# Sheet2.net
KiCad netlist of a schematic drawn in Altium Designer
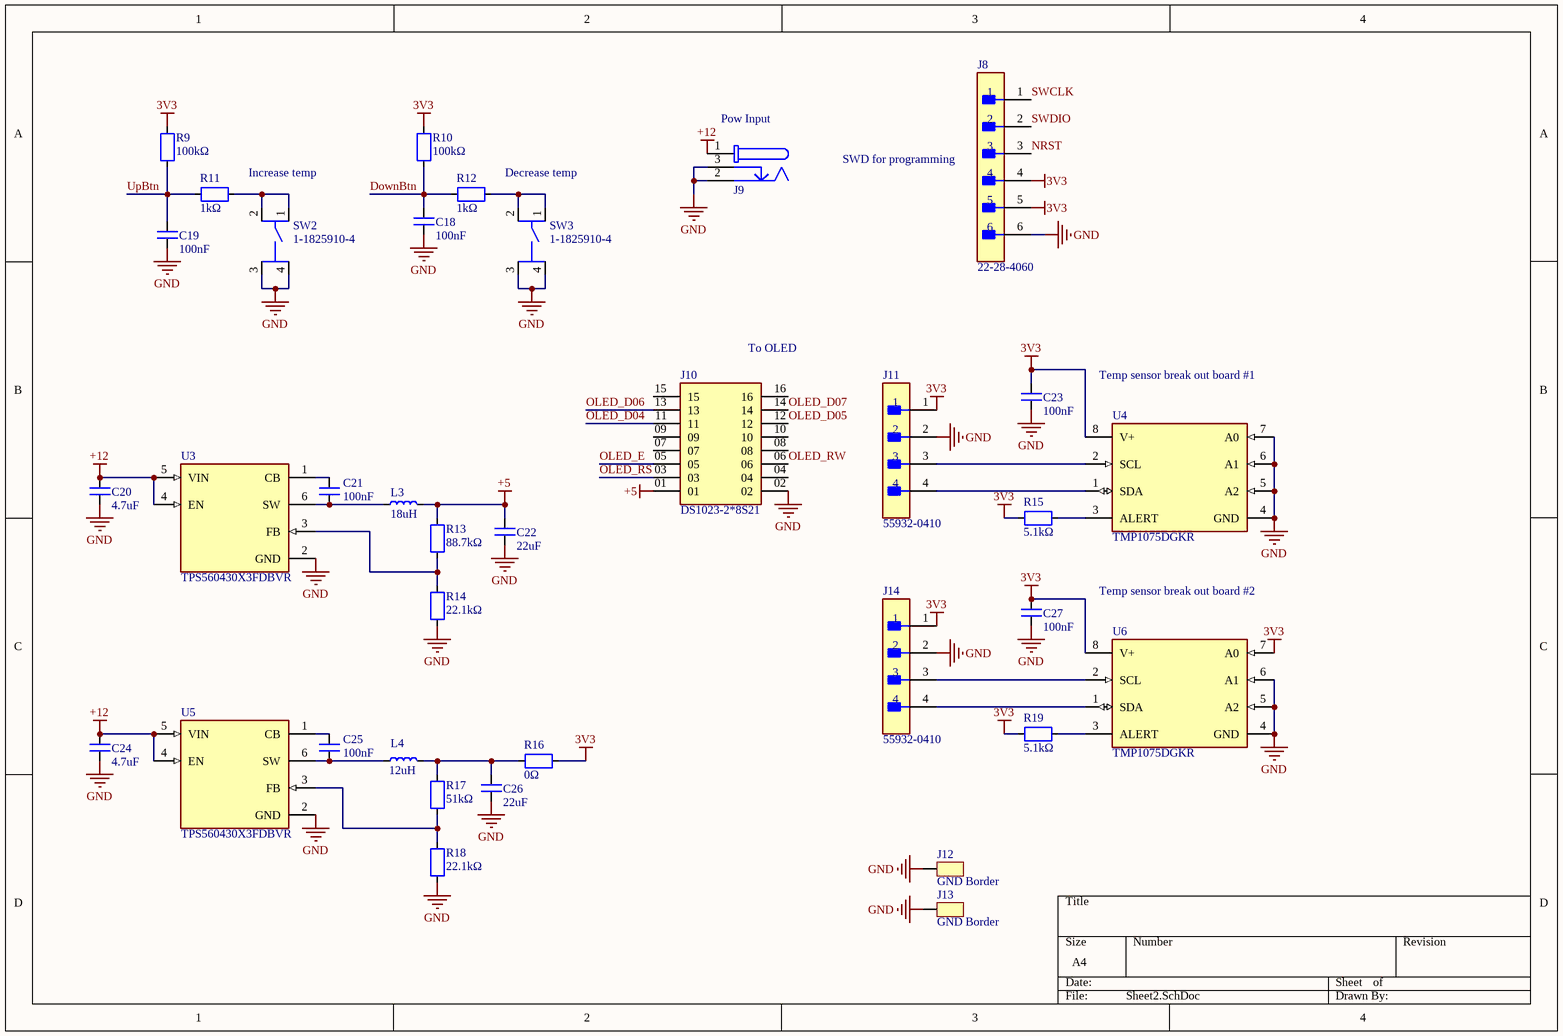
[diagram p0: Sheet2.SchDoc]

(export (version "E")
  (design (tool "Eeschema 10.0.6"))
  (components
    (comp (ref "C18") (value "100nF") (footprint "0603 Imperial") (libsource (lib "Schlib1") (part "0603 C")))
    (comp (ref "C19") (value "100nF") (footprint "0603 Imperial") (libsource (lib "Schlib1") (part "0603 C")))
    (comp (ref "C20") (value "4.7uF") (footprint "0603 Imperial") (libsource (lib "Schlib1") (part "0603 C")))
    (comp (ref "C21") (value "100nF") (footprint "0603 Imperial") (libsource (lib "Schlib1") (part "0603 C")))
    (comp (ref "C22") (value "22uF") (footprint "0603 Imperial") (libsource (lib "Schlib1") (part "0603 C")))
    (comp (ref "C23") (value "100nF") (footprint "0603 Imperial") (libsource (lib "Schlib1") (part "0603 C")))
    (comp (ref "C24") (value "4.7uF") (footprint "0603 Imperial") (libsource (lib "Schlib1") (part "0603 C")))
    (comp (ref "C25") (value "100nF") (footprint "0603 Imperial") (libsource (lib "Schlib1") (part "0603 C")))
    (comp (ref "C26") (value "22uF") (footprint "0603 Imperial") (libsource (lib "Schlib1") (part "0603 C")))
    (comp (ref "C27") (value "100nF") (footprint "0603 Imperial") (libsource (lib "Schlib1") (part "0603 C")))
    (comp (ref "J8")
      (value "22-28-4060")
      (footprint "FP-22-28-4060-MFG")
      (description "CONN HEADER VERT 6POS 2.54MM")
      (libsource (lib "Schlib1") (part "6 pin header"))
    )
    (comp (ref "J9")
      (value "694106105102")
      (footprint "694108105102")
      (description "WR-DC DC Power Jack Connector, Male, Right Angled, 24V, 5A")
      (fields (field (name "MANUFACTURER") "Wurth Elektronik"))
      (libsource (lib "Schlib1") (part "694106105102"))
    )
    (comp (ref "J10")
      (value "DS1023-2*8S21")
      (footprint "16 pin header")
      (description "SSQ - Samtec 2.54mm Square Tail Dual Row Socket Strip 8.5mm Profile - Fast Stock")
      (fields (field (name "MF") "Samtec") (field (name "MP") "SSQ-108-XX-X-D"))
      (libsource (lib "Schlib1") (part "DS1023-2*8S21"))
    )
    (comp (ref "J11")
      (value "55932-0410")
      (footprint "Wire Solder Pads")
      (description "CONN HEADER VERT 4POS 2MM")
      (libsource (lib "Schlib1") (part "Wire Solder pads"))
    )
    (comp (ref "J12")
      (value "GND Border")
      (footprint "GND Border")
      (libsource (lib "Schlib1") (part "GND Border"))
    )
    (comp (ref "J13")
      (value "GND Border")
      (footprint "GND Border")
      (libsource (lib "Schlib1") (part "GND Border"))
    )
    (comp (ref "J14")
      (value "55932-0410")
      (footprint "Wire Solder Pads")
      (description "CONN HEADER VERT 4POS 2MM")
      (libsource (lib "Schlib1") (part "Wire Solder pads"))
    )
    (comp (ref "L3")
      (value "18uH")
      (footprint "IND_SRR6038-180Y")
      (description "Ind6.8x6.8x3.8mm,18uH30%1.5A,shdSMD ¦ Bourns SRR6038-180Y")
      (fields (field (name "MF") "Bourns") (field (name "MP") "SRR6038-180Y"))
      (libsource (lib "Schlib1") (part "18uH"))
    )
    (comp (ref "L4")
      (value "12uH")
      (footprint "WE-PD2SR_7850")
      (description "WE-PD2SR SMT Power Inductor, size 7850, 1.2µH, 4.85A, 13mΩ")
      (fields
        (field (name "MANUFACTURER PART NUMBER") "744787012")
        (field (name "MANUFACTURER") "Wurth Elektronik")
      )
      (libsource (lib "Schlib1") (part "12uH"))
    )
    (comp (ref "R9") (value "100kΩ") (footprint "0603 Imperial") (libsource (lib "Schlib1") (part "0603 R")))
    (comp (ref "R10") (value "100kΩ") (footprint "0603 Imperial") (libsource (lib "Schlib1") (part "0603 R")))
    (comp (ref "R11") (value "1kΩ") (footprint "0603 Imperial") (libsource (lib "Schlib1") (part "0603 R")))
    (comp (ref "R12") (value "1kΩ") (footprint "0603 Imperial") (libsource (lib "Schlib1") (part "0603 R")))
    (comp (ref "R13")
      (value "88.7kΩ")
      (footprint "0603 Imperial")
      (libsource (lib "Schlib1") (part "0603 R"))
    )
    (comp (ref "R14")
      (value "22.1kΩ")
      (footprint "0603 Imperial")
      (libsource (lib "Schlib1") (part "0603 R"))
    )
    (comp (ref "R15") (value "5.1kΩ") (footprint "0603 Imperial") (libsource (lib "Schlib1") (part "0603 R")))
    (comp (ref "R16") (value "0Ω") (footprint "0603 Imperial") (libsource (lib "Schlib1") (part "0603 R")))
    (comp (ref "R17") (value "51kΩ") (footprint "0603 Imperial") (libsource (lib "Schlib1") (part "0603 R")))
    (comp (ref "R18")
      (value "22.1kΩ")
      (footprint "0603 Imperial")
      (libsource (lib "Schlib1") (part "0603 R"))
    )
    (comp (ref "R19") (value "5.1kΩ") (footprint "0603 Imperial") (libsource (lib "Schlib1") (part "0603 R")))
    (comp (ref "SW2")
      (value "1-1825910-4")
      (footprint "TE_1-1825910-4")
      (description "Switch Tactile OFF _ON_ SPST Round Button PC Pins 0.05A 24VDC 100000Cycles 1.56N Thru-Hole")
      (fields (field (name "MF") "TE Connectivity"))
      (libsource (lib "Schlib1") (part "1-1825910-4"))
    )
    (comp (ref "SW3")
      (value "1-1825910-4")
      (footprint "TE_1-1825910-4")
      (description "Switch Tactile OFF _ON_ SPST Round Button PC Pins 0.05A 24VDC 100000Cycles 1.56N Thru-Hole")
      (fields (field (name "MF") "TE Connectivity"))
      (libsource (lib "Schlib1") (part "1-1825910-4"))
    )
    (comp (ref "U3")
      (value "TPS560430X3FDBVR")
      (footprint "Buck")
      (fields (field (name "MF") "{'manufacturer': u'Texas Instruments'}"))
      (libsource (lib "Schlib1") (part "Buck"))
    )
    (comp (ref "U4")
      (value "TMP1075DGKR")
      (footprint "FP-DGK0008A-IPC_A")
      (description "SENSOR TEMPERATURE")
      (libsource (lib "Schlib1") (part "CMP-04948-000063-1"))
    )
    (comp (ref "U5")
      (value "TPS560430X3FDBVR")
      (footprint "Buck")
      (fields (field (name "MF") "{'manufacturer': u'Texas Instruments'}"))
      (libsource (lib "Schlib1") (part "Buck"))
    )
    (comp (ref "U6")
      (value "TMP1075DGKR")
      (footprint "FP-DGK0008A-IPC_A")
      (description "SENSOR TEMPERATURE")
      (libsource (lib "Schlib1") (part "CMP-04948-000063-1"))
    )
  )
  (nets
    (net (code "1") (name "+5") (class "Default")
      (node (ref "C22") (pin "1") (pinfunction "1_1") (pintype "passive"))
      (node (ref "J10") (pin "01") (pinfunction "01_01") (pintype "passive"))
      (node (ref "L3") (pin "2") (pinfunction "2_2") (pintype "passive"))
      (node (ref "R13") (pin "2") (pinfunction "2_2") (pintype "passive"))
    )
    (net (code "2") (name "+12") (class "Default")
      (node (ref "C20") (pin "1") (pinfunction "1_1") (pintype "passive"))
      (node (ref "C24") (pin "1") (pinfunction "1_1") (pintype "passive"))
      (node (ref "J9") (pin "1") (pinfunction "1_1") (pintype "passive"))
      (node (ref "U3") (pin "4") (pinfunction "EN_4") (pintype "input"))
      (node (ref "U3") (pin "5") (pinfunction "VIN_5") (pintype "input"))
      (node (ref "U5") (pin "4") (pinfunction "EN_4") (pintype "input"))
      (node (ref "U5") (pin "5") (pinfunction "VIN_5") (pintype "input"))
    )
    (net (code "3") (name "/DownBtn") (class "Default")
      (node (ref "C18") (pin "1") (pinfunction "1_1") (pintype "passive"))
      (node (ref "R10") (pin "1") (pinfunction "1_1") (pintype "passive"))
      (node (ref "R12") (pin "2") (pinfunction "2_2") (pintype "passive"))
    )
    (net (code "4") (name "/NRST") (class "Default")
      (node (ref "J8") (pin "3") (pinfunction "3_3") (pintype "passive"))
    )
    (net (code "5") (name "/OLED_D04") (class "Default")
      (node (ref "J10") (pin "11") (pinfunction "11_11") (pintype "passive"))
    )
    (net (code "6") (name "/OLED_D05") (class "Default")
      (node (ref "J10") (pin "12") (pinfunction "12_12") (pintype "passive"))
    )
    (net (code "7") (name "/OLED_D06") (class "Default")
      (node (ref "J10") (pin "13") (pinfunction "13_13") (pintype "passive"))
    )
    (net (code "8") (name "/OLED_D07") (class "Default")
      (node (ref "J10") (pin "14") (pinfunction "14_14") (pintype "passive"))
    )
    (net (code "9") (name "/OLED_E") (class "Default")
      (node (ref "J10") (pin "05") (pinfunction "05_05") (pintype "passive"))
    )
    (net (code "10") (name "/OLED_RS") (class "Default")
      (node (ref "J10") (pin "03") (pinfunction "03_03") (pintype "passive"))
    )
    (net (code "11") (name "/OLED_RW") (class "Default")
      (node (ref "J10") (pin "06") (pinfunction "06_06") (pintype "passive"))
    )
    (net (code "12") (name "/SWCLK") (class "Default")
      (node (ref "J8") (pin "1") (pinfunction "1_1") (pintype "passive"))
    )
    (net (code "13") (name "/SWDIO") (class "Default")
      (node (ref "J8") (pin "2") (pinfunction "2_2") (pintype "passive"))
    )
    (net (code "14") (name "/UpBtn") (class "Default")
      (node (ref "C19") (pin "1") (pinfunction "1_1") (pintype "passive"))
      (node (ref "R11") (pin "2") (pinfunction "2_2") (pintype "passive"))
      (node (ref "R9") (pin "1") (pinfunction "1_1") (pintype "passive"))
    )
    (net (code "15") (name "3V3") (class "Default")
      (node (ref "C23") (pin "2") (pinfunction "2_2") (pintype "passive"))
      (node (ref "C27") (pin "2") (pinfunction "2_2") (pintype "passive"))
      (node (ref "J11") (pin "1") (pinfunction "1_1") (pintype "passive"))
      (node (ref "J14") (pin "1") (pinfunction "1_1") (pintype "passive"))
      (node (ref "J8") (pin "4") (pinfunction "4_4") (pintype "passive"))
      (node (ref "J8") (pin "5") (pinfunction "5_5") (pintype "passive"))
      (node (ref "R10") (pin "2") (pinfunction "2_2") (pintype "passive"))
      (node (ref "R15") (pin "2") (pinfunction "2_2") (pintype "passive"))
      (node (ref "R16") (pin "2") (pinfunction "2_2") (pintype "passive"))
      (node (ref "R19") (pin "2") (pinfunction "2_2") (pintype "passive"))
      (node (ref "R9") (pin "2") (pinfunction "2_2") (pintype "passive"))
      (node (ref "U4") (pin "8") (pinfunction "V+_8") (pintype "power_in"))
      (node (ref "U6") (pin "7") (pinfunction "A0_7") (pintype "input"))
      (node (ref "U6") (pin "8") (pinfunction "V+_8") (pintype "power_in"))
    )
    (net (code "16") (name "GND") (class "Default")
      (node (ref "C18") (pin "2") (pinfunction "2_2") (pintype "passive"))
      (node (ref "C19") (pin "2") (pinfunction "2_2") (pintype "passive"))
      (node (ref "C20") (pin "2") (pinfunction "2_2") (pintype "passive"))
      (node (ref "C22") (pin "2") (pinfunction "2_2") (pintype "passive"))
      (node (ref "C23") (pin "1") (pinfunction "1_1") (pintype "passive"))
      (node (ref "C24") (pin "2") (pinfunction "2_2") (pintype "passive"))
      (node (ref "C26") (pin "2") (pinfunction "2_2") (pintype "passive"))
      (node (ref "C27") (pin "1") (pinfunction "1_1") (pintype "passive"))
      (node (ref "J10") (pin "02") (pinfunction "02_02") (pintype "passive"))
      (node (ref "J11") (pin "2") (pinfunction "2_2") (pintype "passive"))
      (node (ref "J12") (pin "0") (pinfunction "0_0") (pintype "passive"))
      (node (ref "J13") (pin "0") (pinfunction "0_0") (pintype "passive"))
      (node (ref "J14") (pin "2") (pinfunction "2_2") (pintype "passive"))
      (node (ref "J8") (pin "6") (pinfunction "6_6") (pintype "passive"))
      (node (ref "J9") (pin "2") (pinfunction "2_2") (pintype "passive"))
      (node (ref "J9") (pin "3") (pinfunction "3_3") (pintype "passive"))
      (node (ref "R14") (pin "1") (pinfunction "1_1") (pintype "passive"))
      (node (ref "R18") (pin "1") (pinfunction "1_1") (pintype "passive"))
      (node (ref "SW2") (pin "3") (pinfunction "3_3") (pintype "passive"))
      (node (ref "SW2") (pin "4") (pinfunction "4_4") (pintype "passive"))
      (node (ref "SW3") (pin "3") (pinfunction "3_3") (pintype "passive"))
      (node (ref "SW3") (pin "4") (pinfunction "4_4") (pintype "passive"))
      (node (ref "U3") (pin "2") (pinfunction "GND_2") (pintype "power_in"))
      (node (ref "U4") (pin "4") (pinfunction "GND_4") (pintype "power_in"))
      (node (ref "U4") (pin "5") (pinfunction "A2_5") (pintype "input"))
      (node (ref "U4") (pin "6") (pinfunction "A1_6") (pintype "input"))
      (node (ref "U4") (pin "7") (pinfunction "A0_7") (pintype "input"))
      (node (ref "U5") (pin "2") (pinfunction "GND_2") (pintype "power_in"))
      (node (ref "U6") (pin "4") (pinfunction "GND_4") (pintype "power_in"))
      (node (ref "U6") (pin "5") (pinfunction "A2_5") (pintype "input"))
      (node (ref "U6") (pin "6") (pinfunction "A1_6") (pintype "input"))
    )
    (net (code "17") (name "Net-(C26-Pad1)") (class "Default")
      (node (ref "C26") (pin "1") (pinfunction "1_1") (pintype "passive"))
      (node (ref "L4") (pin "2") (pinfunction "2_2") (pintype "passive"))
      (node (ref "R16") (pin "1") (pinfunction "1_1") (pintype "passive"))
      (node (ref "R17") (pin "2") (pinfunction "2_2") (pintype "passive"))
    )
    (net (code "18") (name "Net-(R11-Pad1)") (class "Default")
      (node (ref "R11") (pin "1") (pinfunction "1_1") (pintype "passive"))
      (node (ref "SW2") (pin "1") (pinfunction "1_1") (pintype "passive"))
      (node (ref "SW2") (pin "2") (pinfunction "2_2") (pintype "passive"))
    )
    (net (code "19") (name "Net-(R12-Pad1)") (class "Default")
      (node (ref "R12") (pin "1") (pinfunction "1_1") (pintype "passive"))
      (node (ref "SW3") (pin "1") (pinfunction "1_1") (pintype "passive"))
      (node (ref "SW3") (pin "2") (pinfunction "2_2") (pintype "passive"))
    )
    (net (code "20") (name "Net-(U3-CB)") (class "Default")
      (node (ref "C21") (pin "1") (pinfunction "1_1") (pintype "passive"))
      (node (ref "U3") (pin "1") (pinfunction "CB_1") (pintype "passive"))
    )
    (net (code "21") (name "Net-(U3-FB)") (class "Default")
      (node (ref "R13") (pin "1") (pinfunction "1_1") (pintype "passive"))
      (node (ref "R14") (pin "2") (pinfunction "2_2") (pintype "passive"))
      (node (ref "U3") (pin "3") (pinfunction "FB_3") (pintype "input"))
    )
    (net (code "22") (name "Net-(U3-SW)") (class "Default")
      (node (ref "C21") (pin "2") (pinfunction "2_2") (pintype "passive"))
      (node (ref "L3") (pin "1") (pinfunction "1_1") (pintype "passive"))
      (node (ref "U3") (pin "6") (pinfunction "SW_6") (pintype "passive"))
    )
    (net (code "23") (name "Net-(U4-ALERT)") (class "Default")
      (node (ref "R15") (pin "1") (pinfunction "1_1") (pintype "passive"))
      (node (ref "U4") (pin "3") (pinfunction "ALERT_3") (pintype "open_collector"))
    )
    (net (code "24") (name "Net-(U4-SCL)") (class "Default")
      (node (ref "J11") (pin "3") (pinfunction "3_3") (pintype "passive"))
      (node (ref "U4") (pin "2") (pinfunction "SCL_2") (pintype "input"))
    )
    (net (code "25") (name "Net-(U4-SDA)") (class "Default")
      (node (ref "J11") (pin "4") (pinfunction "4_4") (pintype "passive"))
      (node (ref "U4") (pin "1") (pinfunction "SDA_1") (pintype "bidirectional"))
    )
    (net (code "26") (name "Net-(U5-CB)") (class "Default")
      (node (ref "C25") (pin "1") (pinfunction "1_1") (pintype "passive"))
      (node (ref "U5") (pin "1") (pinfunction "CB_1") (pintype "passive"))
    )
    (net (code "27") (name "Net-(U5-FB)") (class "Default")
      (node (ref "R17") (pin "1") (pinfunction "1_1") (pintype "passive"))
      (node (ref "R18") (pin "2") (pinfunction "2_2") (pintype "passive"))
      (node (ref "U5") (pin "3") (pinfunction "FB_3") (pintype "input"))
    )
    (net (code "28") (name "Net-(U5-SW)") (class "Default")
      (node (ref "C25") (pin "2") (pinfunction "2_2") (pintype "passive"))
      (node (ref "L4") (pin "1") (pinfunction "1_1") (pintype "passive"))
      (node (ref "U5") (pin "6") (pinfunction "SW_6") (pintype "passive"))
    )
    (net (code "29") (name "Net-(U6-ALERT)") (class "Default")
      (node (ref "R19") (pin "1") (pinfunction "1_1") (pintype "passive"))
      (node (ref "U6") (pin "3") (pinfunction "ALERT_3") (pintype "open_collector"))
    )
    (net (code "30") (name "Net-(U6-SCL)") (class "Default")
      (node (ref "J14") (pin "3") (pinfunction "3_3") (pintype "passive"))
      (node (ref "U6") (pin "2") (pinfunction "SCL_2") (pintype "input"))
    )
    (net (code "31") (name "Net-(U6-SDA)") (class "Default")
      (node (ref "J14") (pin "4") (pinfunction "4_4") (pintype "passive"))
      (node (ref "U6") (pin "1") (pinfunction "SDA_1") (pintype "bidirectional"))
    )
    (net (code "32") (name "unconnected-(J10-Pad04)") (class "Default")
      (node (ref "J10") (pin "04") (pinfunction "04_04") (pintype "passive"))
    )
    (net (code "33") (name "unconnected-(J10-Pad07)") (class "Default")
      (node (ref "J10") (pin "07") (pinfunction "07_07") (pintype "passive"))
    )
    (net (code "34") (name "unconnected-(J10-Pad08)") (class "Default")
      (node (ref "J10") (pin "08") (pinfunction "08_08") (pintype "passive"))
    )
    (net (code "35") (name "unconnected-(J10-Pad09)") (class "Default")
      (node (ref "J10") (pin "09") (pinfunction "09_09") (pintype "passive"))
    )
    (net (code "36") (name "unconnected-(J10-Pad10)") (class "Default")
      (node (ref "J10") (pin "10") (pinfunction "10_10") (pintype "passive"))
    )
    (net (code "37") (name "unconnected-(J10-Pad15)") (class "Default")
      (node (ref "J10") (pin "15") (pinfunction "15_15") (pintype "passive"))
    )
    (net (code "38") (name "unconnected-(J10-Pad16)") (class "Default")
      (node (ref "J10") (pin "16") (pinfunction "16_16") (pintype "passive"))
    )
  )
)
